# 9_1_2_1_detector.net
KiCad netlist of a schematic drawn in EAGLE
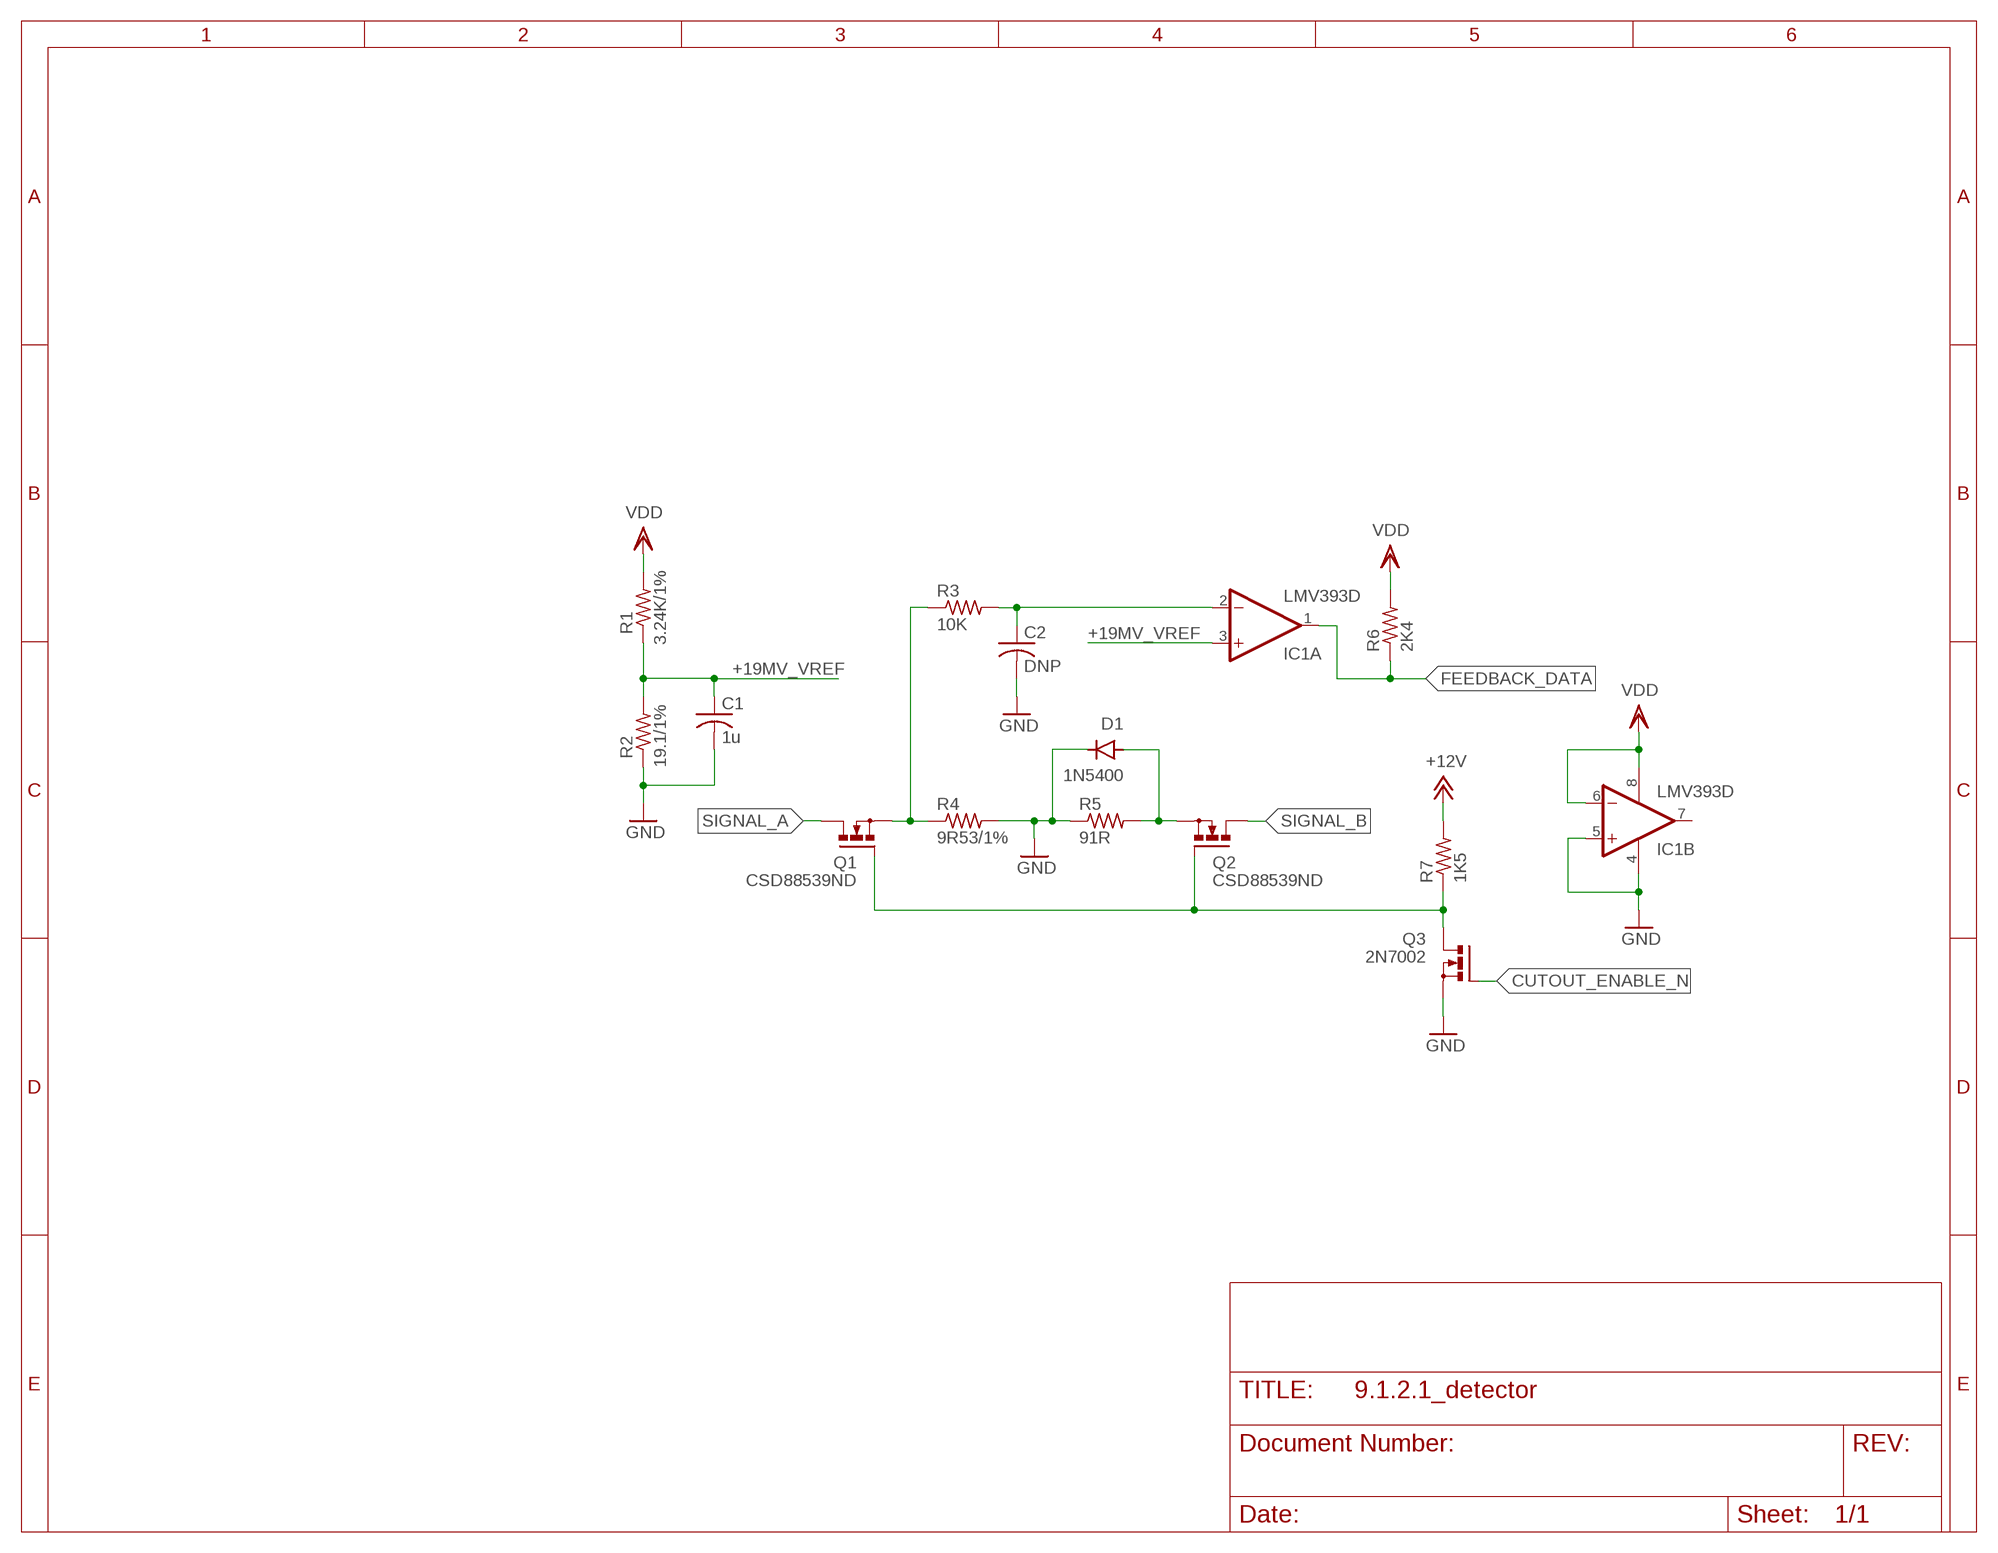
[diagram p0: schematic, sheet 1]

(export (version "E")
  (design (tool "Eeschema 10.0.6"))
  (components
    (comp (ref "C1")
      (value "1u")
      (footprint "eagle-import:C0402")
      (libsource (lib "eagle-import") (part "C-USC0402"))
    )
    (comp (ref "C2")
      (value "DNP")
      (footprint "eagle-import:C0402")
      (libsource (lib "eagle-import") (part "C-USC0402"))
    )
    (comp (ref "D1")
      (value "1N5400")
      (footprint "eagle-import:DO201-15")
      (libsource (lib "eagle-import") (part "1N5400"))
    )
    (comp (ref "IC1")
      (value "LMV393D")
      (footprint "eagle-import:SO08")
      (libsource (lib "eagle-import") (part "LM393D"))
    )
    (comp (ref "Q1")
      (value "CSD88539ND")
      (footprint "eagle-import:TO220BV")
      (libsource (lib "eagle-import") (part "IRF512"))
    )
    (comp (ref "Q2")
      (value "CSD88539ND")
      (footprint "eagle-import:TO220BV")
      (libsource (lib "eagle-import") (part "IRF512"))
    )
    (comp (ref "Q3")
      (value "2N7002")
      (footprint "eagle-import:TO220BV")
      (libsource (lib "eagle-import") (part "IRF512"))
    )
    (comp (ref "R1")
      (value "3.24K/1%")
      (footprint "eagle-import:R0402")
      (libsource (lib "eagle-import") (part "R-US_R0402"))
    )
    (comp (ref "R2")
      (value "19.1/1%")
      (footprint "eagle-import:R0402")
      (libsource (lib "eagle-import") (part "R-US_R0402"))
    )
    (comp (ref "R3")
      (value "10K")
      (footprint "eagle-import:R0402")
      (libsource (lib "eagle-import") (part "R-US_R0402"))
    )
    (comp (ref "R4")
      (value "9R53/1%")
      (footprint "eagle-import:R1206")
      (libsource (lib "eagle-import") (part "R-US_R1206"))
    )
    (comp (ref "R5")
      (value "91R")
      (footprint "eagle-import:R1206")
      (libsource (lib "eagle-import") (part "R-US_R1206"))
    )
    (comp (ref "R6")
      (value "2K4")
      (footprint "eagle-import:R0402")
      (libsource (lib "eagle-import") (part "R-US_R0402"))
    )
    (comp (ref "R7")
      (value "1K5")
      (footprint "eagle-import:R1206")
      (libsource (lib "eagle-import") (part "R-US_R1206"))
    )
  )
  (nets
    (net (code "1") (name "+12V") (class "Default")
      (node (ref "R7") (pin "2") (pinfunction "2_2") (pintype "passive"))
    )
    (net (code "2") (name "/+19MV_VREF") (class "Default")
      (node (ref "C1") (pin "1") (pinfunction "1_1") (pintype "passive"))
      (node (ref "IC1") (pin "3") (pinfunction "+IN_3") (pintype "input"))
      (node (ref "R1") (pin "1") (pinfunction "1_1") (pintype "passive"))
      (node (ref "R2") (pin "2") (pinfunction "2_2") (pintype "passive"))
    )
    (net (code "3") (name "CUTOUT_ENABLE_N") (class "Default")
      (node (ref "Q3") (pin "G") (pinfunction "G_G") (pintype "passive"))
    )
    (net (code "4") (name "FEEDBACK_DATA") (class "Default")
      (node (ref "IC1") (pin "1") (pinfunction "OUT_1") (pintype "output"))
      (node (ref "R6") (pin "1") (pinfunction "1_1") (pintype "passive"))
    )
    (net (code "5") (name "GND") (class "Default")
      (node (ref "C1") (pin "2") (pinfunction "2_2") (pintype "passive"))
      (node (ref "C2") (pin "2") (pinfunction "2_2") (pintype "passive"))
      (node (ref "D1") (pin "C") (pinfunction "C_C") (pintype "passive"))
      (node (ref "IC1") (pin "4") (pinfunction "V-_4") (pintype "power_in"))
      (node (ref "IC1") (pin "5") (pinfunction "+IN_5") (pintype "input"))
      (node (ref "Q3") (pin "S") (pinfunction "S_S") (pintype "passive"))
      (node (ref "R2") (pin "1") (pinfunction "1_1") (pintype "passive"))
      (node (ref "R4") (pin "2") (pinfunction "2_2") (pintype "passive"))
      (node (ref "R5") (pin "1") (pinfunction "1_1") (pintype "passive"))
    )
    (net (code "6") (name "Net-(D1-PadA)") (class "Default")
      (node (ref "D1") (pin "A") (pinfunction "A_A") (pintype "passive"))
      (node (ref "Q2") (pin "S") (pinfunction "S_S") (pintype "passive"))
      (node (ref "R5") (pin "2") (pinfunction "2_2") (pintype "passive"))
    )
    (net (code "7") (name "Net-(IC1A--IN)") (class "Default")
      (node (ref "C2") (pin "1") (pinfunction "1_1") (pintype "passive"))
      (node (ref "IC1") (pin "2") (pinfunction "-IN_2") (pintype "input"))
      (node (ref "R3") (pin "2") (pinfunction "2_2") (pintype "passive"))
    )
    (net (code "8") (name "Net-(Q1-PadG)") (class "Default")
      (node (ref "Q1") (pin "G") (pinfunction "G_G") (pintype "passive"))
      (node (ref "Q2") (pin "G") (pinfunction "G_G") (pintype "passive"))
      (node (ref "Q3") (pin "D") (pinfunction "D_D") (pintype "passive"))
      (node (ref "R7") (pin "1") (pinfunction "1_1") (pintype "passive"))
    )
    (net (code "9") (name "Net-(Q1-PadS)") (class "Default")
      (node (ref "Q1") (pin "S") (pinfunction "S_S") (pintype "passive"))
      (node (ref "R3") (pin "1") (pinfunction "1_1") (pintype "passive"))
      (node (ref "R4") (pin "1") (pinfunction "1_1") (pintype "passive"))
    )
    (net (code "10") (name "SIGNAL_A") (class "Default")
      (node (ref "Q1") (pin "D") (pinfunction "D_D") (pintype "passive"))
    )
    (net (code "11") (name "SIGNAL_B") (class "Default")
      (node (ref "Q2") (pin "D") (pinfunction "D_D") (pintype "passive"))
    )
    (net (code "12") (name "VDD") (class "Default")
      (node (ref "IC1") (pin "6") (pinfunction "-IN_6") (pintype "input"))
      (node (ref "IC1") (pin "8") (pinfunction "V+_8") (pintype "power_in"))
      (node (ref "R1") (pin "2") (pinfunction "2_2") (pintype "passive"))
      (node (ref "R6") (pin "2") (pinfunction "2_2") (pintype "passive"))
    )
    (net (code "13") (name "unconnected-(IC1B-OUT-Pad7)") (class "Default")
      (node (ref "IC1") (pin "7") (pinfunction "OUT_7") (pintype "output"))
    )
  )
)
